# PAC_BDD_2.net
KiCad netlist of a schematic drawn in Altium Designer
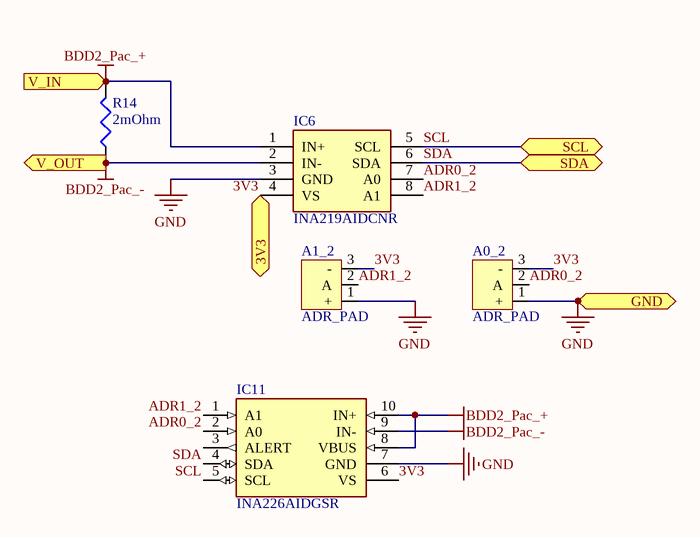
[diagram p0: PAC_BDD_2.SchDoc]

(export (version "E")
  (design (tool "Eeschema 10.0.6"))
  (components
    (comp (ref "A0_2")
      (value "ADR_PAD")
      (footprint "SOLDER_PAD")
      (description "ADR PAD 3 PIN")
      (libsource (lib "SCH_Aquatec") (part "ADR_PAD"))
    )
    (comp (ref "A1_2")
      (value "ADR_PAD")
      (footprint "SOLDER_PAD")
      (description "ADR PAD 3 PIN")
      (libsource (lib "SCH_Aquatec") (part "ADR_PAD"))
    )
    (comp (ref "IC6")
      (value "INA219AIDCNR")
      (footprint "SOT65P280X145-8N")
      (description "Integrated Circuit")
      (fields
        (field (name "MANUFACTURER_PART_NUMBER") "INA219BIDCNR")
        (field (name "MOUSER PART NUMBER") "595-INA219BIDCNR")
      )
      (libsource (lib "*") (part "INA219BIDCNR"))
    )
    (comp (ref "IC11")
      (value "INA226AIDGSR")
      (footprint "SamacSys:SOP50P490X110-10N")
      (description "Integrated Circuit")
      (fields (field (name "MOUSER PART NUMBER") "595-INA226AIDGSR"))
      (libsource (lib "*") (part "INA226AIDGSR"))
    )
    (comp (ref "R14")
      (value "2mOhm")
      (footprint "RESC3216X75N")
      (description "Resistor")
      (fields (field (name "PUBLISHER") "Altium Limited"))
      (libsource (lib "Miscellaneous Devices") (part "Res3"))
    )
  )
  (nets
    (net (code "1") (name "/3V3") (class "Default")
      (node (ref "A0_2") (pin "3") (pinfunction "-_3") (pintype "passive"))
      (node (ref "A1_2") (pin "3") (pinfunction "-_3") (pintype "passive"))
      (node (ref "IC11") (pin "6") (pinfunction "VS_6") (pintype "power_in"))
      (node (ref "IC6") (pin "4") (pinfunction "VS_4") (pintype "power_in"))
    )
    (net (code "2") (name "/ADR0_2") (class "Default")
      (node (ref "A0_2") (pin "2") (pinfunction "A_2") (pintype "passive"))
      (node (ref "IC11") (pin "2") (pinfunction "A0_2") (pintype "input"))
      (node (ref "IC6") (pin "7") (pinfunction "A0_7") (pintype "passive"))
    )
    (net (code "3") (name "/ADR1_2") (class "Default")
      (node (ref "A1_2") (pin "2") (pinfunction "A_2") (pintype "passive"))
      (node (ref "IC11") (pin "1") (pinfunction "A1_1") (pintype "input"))
      (node (ref "IC6") (pin "8") (pinfunction "A1_8") (pintype "passive"))
    )
    (net (code "4") (name "/SCL") (class "Default")
      (node (ref "IC11") (pin "5") (pinfunction "SCL_5") (pintype "bidirectional"))
      (node (ref "IC6") (pin "5") (pinfunction "SCL_5") (pintype "passive"))
    )
    (net (code "5") (name "/SDA") (class "Default")
      (node (ref "IC11") (pin "4") (pinfunction "SDA_4") (pintype "bidirectional"))
      (node (ref "IC6") (pin "6") (pinfunction "SDA_6") (pintype "passive"))
    )
    (net (code "6") (name "BDD2_Pac_+") (class "Default")
      (node (ref "IC11") (pin "10") (pinfunction "IN+_10") (pintype "input"))
      (node (ref "IC11") (pin "8") (pinfunction "VBUS_8") (pintype "input"))
      (node (ref "IC6") (pin "1") (pinfunction "IN+_1") (pintype "passive"))
      (node (ref "R14") (pin "2") (pinfunction "2_2") (pintype "passive"))
    )
    (net (code "7") (name "BDD2_Pac_-") (class "Default")
      (node (ref "IC11") (pin "9") (pinfunction "IN-_9") (pintype "input"))
      (node (ref "IC6") (pin "2") (pinfunction "IN-_2") (pintype "passive"))
      (node (ref "R14") (pin "1") (pinfunction "1_1") (pintype "passive"))
    )
    (net (code "8") (name "GND") (class "Default")
      (node (ref "A0_2") (pin "1") (pinfunction "+_1") (pintype "passive"))
      (node (ref "A1_2") (pin "1") (pinfunction "+_1") (pintype "passive"))
      (node (ref "IC11") (pin "7") (pinfunction "GND_7") (pintype "power_in"))
      (node (ref "IC6") (pin "3") (pinfunction "GND_3") (pintype "power_in"))
    )
    (net (code "9") (name "unconnected-(IC11-ALERT-Pad3)") (class "Default")
      (node (ref "IC11") (pin "3") (pinfunction "ALERT_3") (pintype "output"))
    )
  )
)
